# encoder_counter.net
KiCad netlist of a schematic drawn in EAGLE
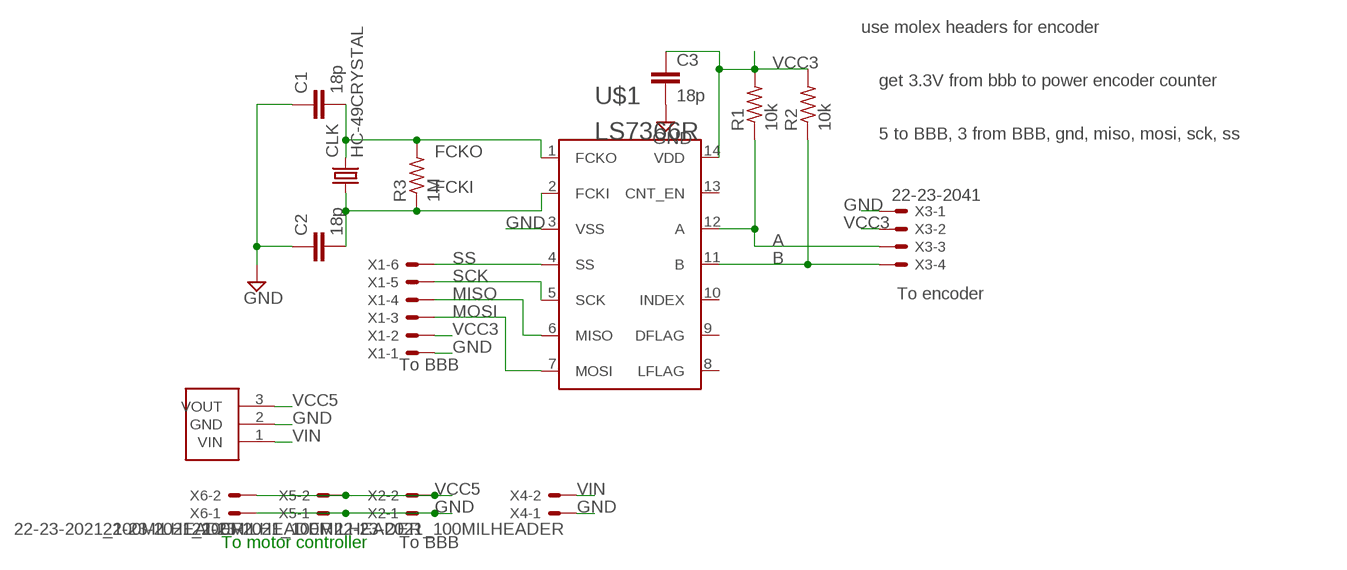
[diagram p0: schematic, sheet 1]

(export (version "E")
  (design (tool "Eeschema 10.0.6"))
  (components
    (comp (ref "C1")
      (value "18p")
      (footprint "eagle-import:C1206")
      (libsource (lib "eagle-import") (part "C-EUC1206"))
    )
    (comp (ref "C2")
      (value "18p")
      (footprint "eagle-import:C1206")
      (libsource (lib "eagle-import") (part "C-EUC1206"))
    )
    (comp (ref "C3")
      (value "18p")
      (footprint "eagle-import:C1206")
      (libsource (lib "eagle-import") (part "C-EUC1206"))
    )
    (comp (ref "CLK")
      (value "HC-49CRYSTAL")
      (footprint "eagle-import:HC49_S")
      (libsource (lib "eagle-import") (part "HC-49CRYSTAL"))
    )
    (comp (ref "R1")
      (value "10k")
      (footprint "eagle-import:R1206")
      (libsource (lib "eagle-import") (part "R-US_R1206"))
    )
    (comp (ref "R2")
      (value "10k")
      (footprint "eagle-import:R1206")
      (libsource (lib "eagle-import") (part "R-US_R1206"))
    )
    (comp (ref "R3")
      (value "1M")
      (footprint "eagle-import:R1206")
      (libsource (lib "eagle-import") (part "R-US_R1206"))
    )
    (comp (ref "U$1")
      (value "LS7366R")
      (footprint "eagle-import:SO14")
      (libsource (lib "eagle-import") (part "LS7366R"))
    )
    (comp (ref "U$3")
      (value "OKI-78SR-X_3PIN-DCDC")
      (footprint "eagle-import:MA03-1")
      (libsource (lib "eagle-import") (part "OKI-78SR-X_3PIN-DCDC"))
    )
    (comp (ref "X1")
      (value "22-23-2061")
      (footprint "eagle-import:22-23-2061")
      (fields (field (name "MF") "MOLEX"))
      (libsource (lib "eagle-import") (part "22-23-2061"))
    )
    (comp (ref "X2")
      (value "22-23-2021_100MILHEADER")
      (footprint "eagle-import:22-23-2021_199MILHEADER")
      (fields (field (name "MF") "MOLEX") (field (name "MPN") "22-23-2021"))
      (libsource (lib "eagle-import") (part "22-23-2021_100MILHEADER"))
    )
    (comp (ref "X3")
      (value "22-23-2041")
      (footprint "eagle-import:22-23-2041")
      (fields (field (name "MF") "MOLEX"))
      (libsource (lib "eagle-import") (part "22-23-2041"))
    )
    (comp (ref "X4")
      (value "22-23-2021_100MILHEADER")
      (footprint "eagle-import:22-23-2021_199MILHEADER")
      (fields (field (name "MF") "MOLEX") (field (name "MPN") "22-23-2021"))
      (libsource (lib "eagle-import") (part "22-23-2021_100MILHEADER"))
    )
    (comp (ref "X5")
      (value "22-23-2021_100MILHEADER")
      (footprint "eagle-import:22-23-2021_199MILHEADER")
      (fields (field (name "MF") "MOLEX") (field (name "MPN") "22-23-2021"))
      (libsource (lib "eagle-import") (part "22-23-2021_100MILHEADER"))
    )
    (comp (ref "X6")
      (value "22-23-2021_100MILHEADER")
      (footprint "eagle-import:22-23-2021_199MILHEADER")
      (fields (field (name "MF") "MOLEX") (field (name "MPN") "22-23-2021"))
      (libsource (lib "eagle-import") (part "22-23-2021_100MILHEADER"))
    )
  )
  (nets
    (net (code "1") (name "/A") (class "Default")
      (node (ref "R1") (pin "1") (pinfunction "1_1") (pintype "passive"))
      (node (ref "U$1") (pin "12") (pinfunction "A_12") (pintype "bidirectional"))
      (node (ref "X3") (pin "3") (pinfunction "S_3") (pintype "passive"))
    )
    (net (code "2") (name "/B") (class "Default")
      (node (ref "R2") (pin "1") (pinfunction "1_1") (pintype "passive"))
      (node (ref "U$1") (pin "11") (pinfunction "B_11") (pintype "bidirectional"))
      (node (ref "X3") (pin "4") (pinfunction "S_4") (pintype "passive"))
    )
    (net (code "3") (name "/FCKI") (class "Default")
      (node (ref "C2") (pin "2") (pinfunction "2_2") (pintype "passive"))
      (node (ref "CLK") (pin "1") (pinfunction "1_1") (pintype "passive"))
      (node (ref "R3") (pin "1") (pinfunction "1_1") (pintype "passive"))
      (node (ref "U$1") (pin "2") (pinfunction "FCKI_2") (pintype "bidirectional"))
    )
    (net (code "4") (name "/FCKO") (class "Default")
      (node (ref "C1") (pin "2") (pinfunction "2_2") (pintype "passive"))
      (node (ref "CLK") (pin "2") (pinfunction "2_2") (pintype "passive"))
      (node (ref "R3") (pin "2") (pinfunction "2_2") (pintype "passive"))
      (node (ref "U$1") (pin "1") (pinfunction "FCKO_1") (pintype "bidirectional"))
    )
    (net (code "5") (name "/MISO") (class "Default")
      (node (ref "U$1") (pin "6") (pinfunction "MISO_6") (pintype "bidirectional"))
      (node (ref "X1") (pin "4") (pinfunction "S_4") (pintype "passive"))
    )
    (net (code "6") (name "/MOSI") (class "Default")
      (node (ref "U$1") (pin "7") (pinfunction "MOSI_7") (pintype "bidirectional"))
      (node (ref "X1") (pin "3") (pinfunction "S_3") (pintype "passive"))
    )
    (net (code "7") (name "/SCK") (class "Default")
      (node (ref "U$1") (pin "5") (pinfunction "SCK_5") (pintype "bidirectional"))
      (node (ref "X1") (pin "5") (pinfunction "S_5") (pintype "passive"))
    )
    (net (code "8") (name "/SS") (class "Default")
      (node (ref "U$1") (pin "4") (pinfunction "SS_4") (pintype "bidirectional"))
      (node (ref "X1") (pin "6") (pinfunction "S_6") (pintype "passive"))
    )
    (net (code "9") (name "/VCC3") (class "Default")
      (node (ref "C3") (pin "1") (pinfunction "1_1") (pintype "passive"))
      (node (ref "R1") (pin "2") (pinfunction "2_2") (pintype "passive"))
      (node (ref "R2") (pin "2") (pinfunction "2_2") (pintype "passive"))
      (node (ref "U$1") (pin "14") (pinfunction "VDD_14") (pintype "bidirectional"))
      (node (ref "X1") (pin "2") (pinfunction "S_2") (pintype "passive"))
      (node (ref "X3") (pin "2") (pinfunction "S_2") (pintype "passive"))
    )
    (net (code "10") (name "/VCC5") (class "Default")
      (node (ref "U$3") (pin "3") (pinfunction "VOUT_3") (pintype "bidirectional"))
      (node (ref "X2") (pin "2") (pinfunction "S_2") (pintype "passive"))
      (node (ref "X5") (pin "2") (pinfunction "S_2") (pintype "passive"))
      (node (ref "X6") (pin "2") (pinfunction "S_2") (pintype "passive"))
    )
    (net (code "11") (name "/VIN") (class "Default")
      (node (ref "U$3") (pin "1") (pinfunction "VIN_1") (pintype "bidirectional"))
      (node (ref "X4") (pin "2") (pinfunction "S_2") (pintype "passive"))
    )
    (net (code "12") (name "GND") (class "Default")
      (node (ref "C1") (pin "1") (pinfunction "1_1") (pintype "passive"))
      (node (ref "C2") (pin "1") (pinfunction "1_1") (pintype "passive"))
      (node (ref "C3") (pin "2") (pinfunction "2_2") (pintype "passive"))
      (node (ref "U$1") (pin "3") (pinfunction "VSS_3") (pintype "bidirectional"))
      (node (ref "U$3") (pin "2") (pinfunction "GND_2") (pintype "bidirectional"))
      (node (ref "X1") (pin "1") (pinfunction "S_1") (pintype "passive"))
      (node (ref "X2") (pin "1") (pinfunction "S_1") (pintype "passive"))
      (node (ref "X3") (pin "1") (pinfunction "S_1") (pintype "passive"))
      (node (ref "X4") (pin "1") (pinfunction "S_1") (pintype "passive"))
      (node (ref "X5") (pin "1") (pinfunction "S_1") (pintype "passive"))
      (node (ref "X6") (pin "1") (pinfunction "S_1") (pintype "passive"))
    )
    (net (code "13") (name "unconnected-(U$1-CNT_EN-Pad13)") (class "Default")
      (node (ref "U$1") (pin "13") (pinfunction "CNT_EN_13") (pintype "bidirectional"))
    )
    (net (code "14") (name "unconnected-(U$1-DFLAG-Pad9)") (class "Default")
      (node (ref "U$1") (pin "9") (pinfunction "DFLAG_9") (pintype "bidirectional"))
    )
    (net (code "15") (name "unconnected-(U$1-INDEX-Pad10)") (class "Default")
      (node (ref "U$1") (pin "10") (pinfunction "INDEX_10") (pintype "bidirectional"))
    )
    (net (code "16") (name "unconnected-(U$1-LFLAG-Pad8)") (class "Default")
      (node (ref "U$1") (pin "8") (pinfunction "LFLAG_8") (pintype "bidirectional"))
    )
  )
)
